# PANEL.net
KiCad netlist of a schematic drawn in Altium Designer
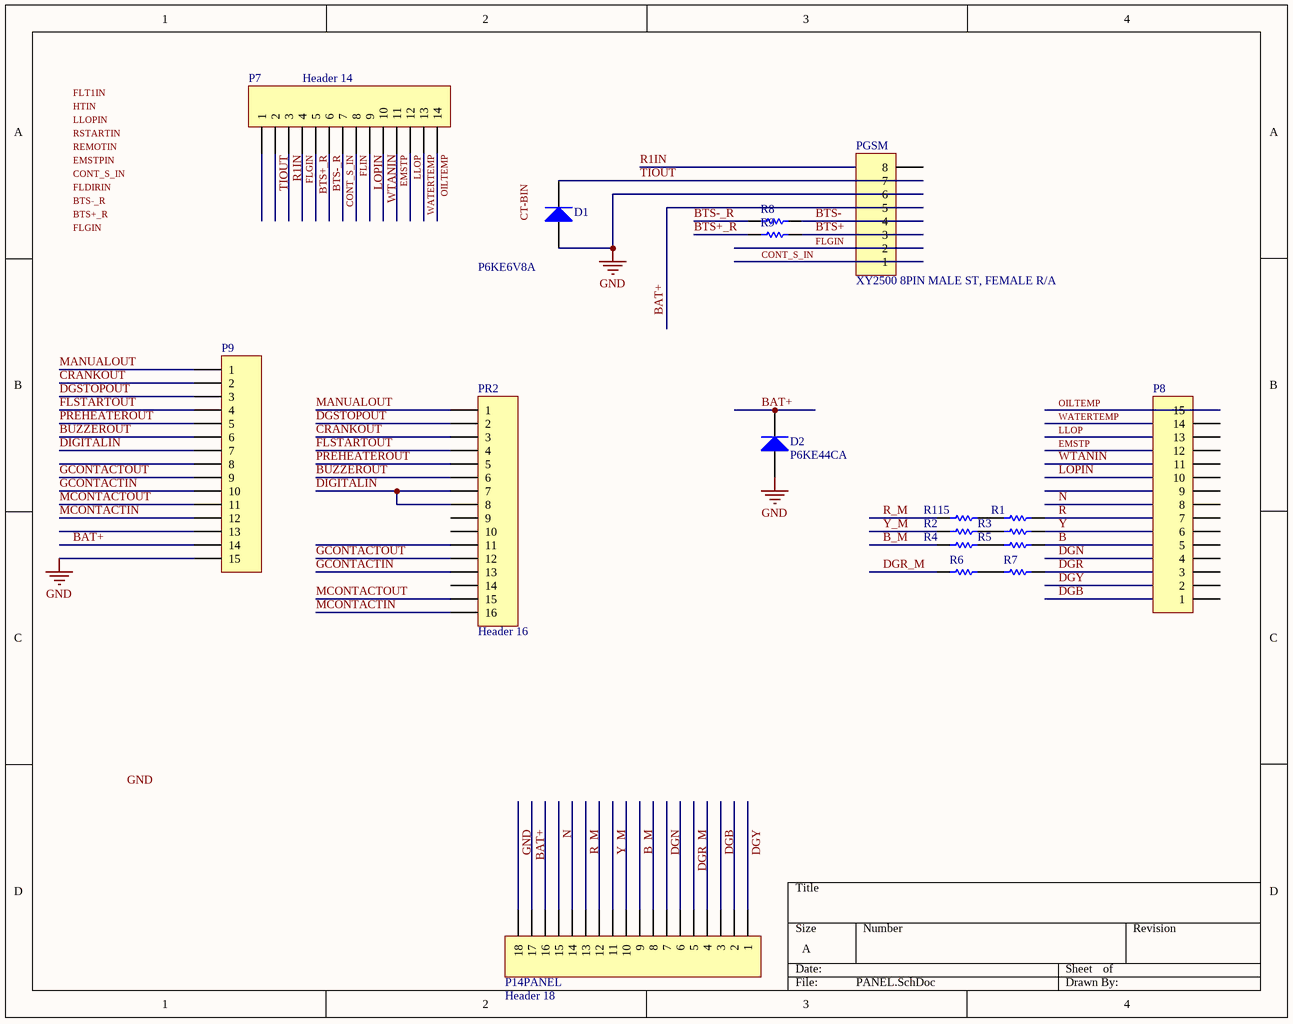
[diagram p0: PANEL.SchDoc]

(export (version "E")
  (design (tool "Eeschema 10.0.6"))
  (components
    (comp (ref "D1")
      (value "P6KE6V8A")
      (footprint "DIODE1A")
      (description "3 Amp Medium Power Silicon Rectifier Diode")
      (fields (field (name "PUBLISHER") "Altium Limited"))
      (libsource (lib "Miscellaneous Devices") (part "Diode 1N5408"))
    )
    (comp (ref "D2")
      (value "P6KE44CA")
      (footprint "DIODE1A")
      (description "3 Amp Medium Power Silicon Rectifier Diode")
      (fields (field (name "PUBLISHER") "Altium Limited"))
      (libsource (lib "Miscellaneous Devices") (part "Diode 1N5408"))
    )
    (comp (ref "P7")
      (value "Header 14")
      (footprint "HDR1X14_BURGE_M")
      (description "Header, 14-Pin")
      (fields (field (name "PUBLISHER") "Altium Limited"))
      (libsource (lib "Miscellaneous Connectors") (part "Header 14"))
    )
    (comp (ref "P8")
      (value "XY2500 7PIN+8PIN MALE ST, FEMALE R/A")
      (footprint "XY2500_15PIN_M_ST")
      (description "Header, 15-Pin")
      (fields (field (name "PUBLISHER") "Altium Limited"))
      (libsource (lib "") (part "Header 15_1"))
    )
    (comp (ref "P9")
      (value "XY2500 7PIN+8PIN MALE ST, FEMALE R/A")
      (footprint "XY2500_15PIN_M_ST")
      (description "Header, 15-Pin")
      (fields (field (name "PUBLISHER") "Altium Limited"))
      (libsource (lib "Miscellaneous Connectors") (part "Header 15"))
    )
    (comp (ref "P14PANEL")
      (value "Header 18")
      (footprint "HDR1X18_BURGE_M")
      (description "Header, 18-Pin")
      (fields (field (name "PUBLISHER") "Altium Limited"))
      (libsource (lib "Miscellaneous Connectors") (part "Header 18"))
    )
    (comp (ref "PGSM")
      (value "XY2500 8PIN MALE ST, FEMALE R/A")
      (footprint "XY2500_8PIN_M_ST")
      (description "Header, 8-Pin")
      (fields (field (name "PUBLISHER") "Altium Limited"))
      (libsource (lib "Miscellaneous Connectors") (part "Header 8"))
    )
    (comp (ref "PR2")
      (value "Header 16")
      (footprint "HDR1X16_BURGE_F")
      (description "Header, 16-Pin")
      (fields (field (name "PUBLISHER") "Altium Limited"))
      (libsource (lib "Miscellaneous Connectors") (part "Header 16"))
    )
    (comp (ref "R1")
      (value "MFR 1M .5W")
      (footprint "AXIAL-0.5")
      (description "Semiconductor Resistor")
      (fields (field (name "PUBLISHER") "Altium Limited"))
      (libsource (lib "Miscellaneous Devices") (part "Res Semi"))
    )
    (comp (ref "R2")
      (value "MFR 1M .5W")
      (footprint "AXIAL-0.5")
      (description "Semiconductor Resistor")
      (fields (field (name "PUBLISHER") "Altium Limited"))
      (libsource (lib "Miscellaneous Devices") (part "Res Semi"))
    )
    (comp (ref "R3")
      (value "MFR 1M .5W")
      (footprint "AXIAL-0.5")
      (description "Semiconductor Resistor")
      (fields (field (name "PUBLISHER") "Altium Limited"))
      (libsource (lib "Miscellaneous Devices") (part "Res Semi"))
    )
    (comp (ref "R4")
      (value "MFR 1M .5W")
      (footprint "AXIAL-0.5")
      (description "Semiconductor Resistor")
      (fields (field (name "PUBLISHER") "Altium Limited"))
      (libsource (lib "Miscellaneous Devices") (part "Res Semi"))
    )
    (comp (ref "R5")
      (value "MFR 1M .5W")
      (footprint "AXIAL-0.5")
      (description "Semiconductor Resistor")
      (fields (field (name "PUBLISHER") "Altium Limited"))
      (libsource (lib "Miscellaneous Devices") (part "Res Semi"))
    )
    (comp (ref "R6")
      (value "MFR 1M .5W")
      (footprint "AXIAL-0.5")
      (description "Semiconductor Resistor")
      (fields (field (name "PUBLISHER") "Altium Limited"))
      (libsource (lib "Miscellaneous Devices") (part "Res Semi"))
    )
    (comp (ref "R7")
      (value "MFR 1M .5W")
      (footprint "AXIAL-0.5")
      (description "Semiconductor Resistor")
      (fields (field (name "PUBLISHER") "Altium Limited"))
      (libsource (lib "Miscellaneous Devices") (part "Res Semi"))
    )
    (comp (ref "R8")
      (value "MFR 1M .5W")
      (footprint "AXIAL-0.5")
      (description "Semiconductor Resistor")
      (fields (field (name "PUBLISHER") "Altium Limited"))
      (libsource (lib "Miscellaneous Devices") (part "Res Semi"))
    )
    (comp (ref "R9")
      (value "MFR 1M .5W")
      (footprint "AXIAL-0.5")
      (description "Semiconductor Resistor")
      (fields (field (name "PUBLISHER") "Altium Limited"))
      (libsource (lib "Miscellaneous Devices") (part "Res Semi"))
    )
    (comp (ref "R115")
      (value "MFR 1M .5W")
      (footprint "AXIAL-0.5")
      (description "Semiconductor Resistor")
      (fields (field (name "PUBLISHER") "Altium Limited"))
      (libsource (lib "Miscellaneous Devices") (part "Res Semi"))
    )
  )
  (nets
    (net (code "1") (name "/B") (class "Default")
      (node (ref "P8") (pin "5") (pinfunction "5_5") (pintype "passive"))
      (node (ref "R5") (pin "2") (pinfunction "2_2") (pintype "passive"))
    )
    (net (code "2") (name "/BAT+") (class "Default")
      (node (ref "D2") (pin "2") (pinfunction "K_2") (pintype "passive"))
      (node (ref "P14PANEL") (pin "17") (pinfunction "17_17") (pintype "passive"))
      (node (ref "P9") (pin "14") (pinfunction "14_14") (pintype "passive"))
      (node (ref "PGSM") (pin "5") (pinfunction "5_5") (pintype "passive"))
    )
    (net (code "3") (name "/BTS+") (class "Default")
      (node (ref "PGSM") (pin "3") (pinfunction "3_3") (pintype "passive"))
      (node (ref "R9") (pin "2") (pinfunction "2_2") (pintype "passive"))
    )
    (net (code "4") (name "/BTS+_R") (class "Default")
      (node (ref "P7") (pin "5") (pinfunction "5_5") (pintype "passive"))
      (node (ref "R9") (pin "1") (pinfunction "1_1") (pintype "passive"))
    )
    (net (code "5") (name "/BTS-") (class "Default")
      (node (ref "PGSM") (pin "4") (pinfunction "4_4") (pintype "passive"))
      (node (ref "R8") (pin "2") (pinfunction "2_2") (pintype "passive"))
    )
    (net (code "6") (name "/BTS-_R") (class "Default")
      (node (ref "P7") (pin "6") (pinfunction "6_6") (pintype "passive"))
      (node (ref "R8") (pin "1") (pinfunction "1_1") (pintype "passive"))
    )
    (net (code "7") (name "/BUZZEROUT") (class "Default")
      (node (ref "P9") (pin "6") (pinfunction "6_6") (pintype "passive"))
      (node (ref "PR2") (pin "6") (pinfunction "6_6") (pintype "passive"))
    )
    (net (code "8") (name "/B_M") (class "Default")
      (node (ref "P14PANEL") (pin "9") (pinfunction "9_9") (pintype "passive"))
      (node (ref "R4") (pin "1") (pinfunction "1_1") (pintype "passive"))
    )
    (net (code "9") (name "/CONT_S_IN") (class "Default")
      (node (ref "P7") (pin "7") (pinfunction "7_7") (pintype "passive"))
      (node (ref "PGSM") (pin "1") (pinfunction "1_1") (pintype "passive"))
    )
    (net (code "10") (name "/CRANKOUT") (class "Default")
      (node (ref "P9") (pin "2") (pinfunction "2_2") (pintype "passive"))
      (node (ref "PR2") (pin "3") (pinfunction "3_3") (pintype "passive"))
    )
    (net (code "12") (name "/DGB") (class "Default")
      (node (ref "P14PANEL") (pin "3") (pinfunction "3_3") (pintype "passive"))
      (node (ref "P8") (pin "1") (pinfunction "1_1") (pintype "passive"))
    )
    (net (code "13") (name "/DGN") (class "Default")
      (node (ref "P14PANEL") (pin "7") (pinfunction "7_7") (pintype "passive"))
      (node (ref "P8") (pin "4") (pinfunction "4_4") (pintype "passive"))
    )
    (net (code "14") (name "/DGR") (class "Default")
      (node (ref "P8") (pin "3") (pinfunction "3_3") (pintype "passive"))
      (node (ref "R7") (pin "2") (pinfunction "2_2") (pintype "passive"))
    )
    (net (code "15") (name "/DGR_M") (class "Default")
      (node (ref "P14PANEL") (pin "5") (pinfunction "5_5") (pintype "passive"))
      (node (ref "R6") (pin "1") (pinfunction "1_1") (pintype "passive"))
    )
    (net (code "16") (name "/DGSTOPOUT") (class "Default")
      (node (ref "P9") (pin "3") (pinfunction "3_3") (pintype "passive"))
      (node (ref "PR2") (pin "2") (pinfunction "2_2") (pintype "passive"))
    )
    (net (code "17") (name "/DGY") (class "Default")
      (node (ref "P14PANEL") (pin "1") (pinfunction "1_1") (pintype "passive"))
      (node (ref "P8") (pin "2") (pinfunction "2_2") (pintype "passive"))
    )
    (net (code "18") (name "/DIGITALIN") (class "Default")
      (node (ref "P9") (pin "7") (pinfunction "7_7") (pintype "passive"))
      (node (ref "PR2") (pin "7") (pinfunction "7_7") (pintype "passive"))
      (node (ref "PR2") (pin "8") (pinfunction "8_8") (pintype "passive"))
    )
    (net (code "19") (name "/EMSTP") (class "Default")
      (node (ref "P7") (pin "11") (pinfunction "11_11") (pintype "passive"))
      (node (ref "P8") (pin "12") (pinfunction "12_12") (pintype "passive"))
    )
    (net (code "22") (name "/FLGIN") (class "Default")
      (node (ref "P7") (pin "4") (pinfunction "4_4") (pintype "passive"))
      (node (ref "PGSM") (pin "2") (pinfunction "2_2") (pintype "passive"))
    )
    (net (code "23") (name "/FLIN") (class "Default")
      (node (ref "P7") (pin "8") (pinfunction "8_8") (pintype "passive"))
    )
    (net (code "24") (name "/FLSTARTOUT") (class "Default")
      (node (ref "P9") (pin "4") (pinfunction "4_4") (pintype "passive"))
      (node (ref "PR2") (pin "4") (pinfunction "4_4") (pintype "passive"))
    )
    (net (code "26") (name "/GCONTACTIN") (class "Default")
      (node (ref "P9") (pin "10") (pinfunction "10_10") (pintype "passive"))
      (node (ref "PR2") (pin "13") (pinfunction "13_13") (pintype "passive"))
    )
    (net (code "27") (name "/GCONTACTOUT") (class "Default")
      (node (ref "P9") (pin "9") (pinfunction "9_9") (pintype "passive"))
      (node (ref "PR2") (pin "12") (pinfunction "12_12") (pintype "passive"))
    )
    (net (code "29") (name "/LLOP") (class "Default")
      (node (ref "P7") (pin "12") (pinfunction "12_12") (pintype "passive"))
      (node (ref "P8") (pin "13") (pinfunction "13_13") (pintype "passive"))
    )
    (net (code "31") (name "/LOPIN") (class "Default")
      (node (ref "P7") (pin "9") (pinfunction "9_9") (pintype "passive"))
      (node (ref "P8") (pin "10") (pinfunction "10_10") (pintype "passive"))
    )
    (net (code "32") (name "/MANUALOUT") (class "Default")
      (node (ref "P9") (pin "1") (pinfunction "1_1") (pintype "passive"))
      (node (ref "PR2") (pin "1") (pinfunction "1_1") (pintype "passive"))
    )
    (net (code "33") (name "/MCONTACTIN") (class "Default")
      (node (ref "P9") (pin "12") (pinfunction "12_12") (pintype "passive"))
      (node (ref "PR2") (pin "16") (pinfunction "16_16") (pintype "passive"))
    )
    (net (code "34") (name "/MCONTACTOUT") (class "Default")
      (node (ref "P9") (pin "11") (pinfunction "11_11") (pintype "passive"))
      (node (ref "PR2") (pin "15") (pinfunction "15_15") (pintype "passive"))
    )
    (net (code "35") (name "/N") (class "Default")
      (node (ref "P14PANEL") (pin "15") (pinfunction "15_15") (pintype "passive"))
      (node (ref "P8") (pin "8") (pinfunction "8_8") (pintype "passive"))
    )
    (net (code "36") (name "/OILTEMP") (class "Default")
      (node (ref "P7") (pin "14") (pinfunction "14_14") (pintype "passive"))
      (node (ref "P8") (pin "15") (pinfunction "15_15") (pintype "passive"))
    )
    (net (code "37") (name "/PREHEATEROUT") (class "Default")
      (node (ref "P9") (pin "5") (pinfunction "5_5") (pintype "passive"))
      (node (ref "PR2") (pin "5") (pinfunction "5_5") (pintype "passive"))
    )
    (net (code "38") (name "/R") (class "Default")
      (node (ref "P8") (pin "7") (pinfunction "7_7") (pintype "passive"))
      (node (ref "R1") (pin "2") (pinfunction "2_2") (pintype "passive"))
    )
    (net (code "39") (name "/R1IN") (class "Default")
      (node (ref "P7") (pin "3") (pinfunction "3_3") (pintype "passive"))
      (node (ref "PGSM") (pin "8") (pinfunction "8_8") (pintype "passive"))
    )
    (net (code "42") (name "/R_M") (class "Default")
      (node (ref "P14PANEL") (pin "13") (pinfunction "13_13") (pintype "passive"))
      (node (ref "R115") (pin "1") (pinfunction "1_1") (pintype "passive"))
    )
    (net (code "43") (name "/TIOUT") (class "Default")
      (node (ref "D1") (pin "2") (pinfunction "K_2") (pintype "passive"))
      (node (ref "P7") (pin "2") (pinfunction "2_2") (pintype "passive"))
      (node (ref "PGSM") (pin "7") (pinfunction "7_7") (pintype "passive"))
    )
    (net (code "44") (name "/WATERTEMP") (class "Default")
      (node (ref "P7") (pin "13") (pinfunction "13_13") (pintype "passive"))
      (node (ref "P8") (pin "14") (pinfunction "14_14") (pintype "passive"))
    )
    (net (code "45") (name "/WTANIN") (class "Default")
      (node (ref "P7") (pin "10") (pinfunction "10_10") (pintype "passive"))
      (node (ref "P8") (pin "11") (pinfunction "11_11") (pintype "passive"))
    )
    (net (code "46") (name "/Y") (class "Default")
      (node (ref "P8") (pin "6") (pinfunction "6_6") (pintype "passive"))
      (node (ref "R3") (pin "2") (pinfunction "2_2") (pintype "passive"))
    )
    (net (code "47") (name "/Y_M") (class "Default")
      (node (ref "P14PANEL") (pin "11") (pinfunction "11_11") (pintype "passive"))
      (node (ref "R2") (pin "1") (pinfunction "1_1") (pintype "passive"))
    )
    (net (code "48") (name "GND") (class "Default")
      (node (ref "D1") (pin "1") (pinfunction "A_1") (pintype "passive"))
      (node (ref "D2") (pin "1") (pinfunction "A_1") (pintype "passive"))
      (node (ref "P14PANEL") (pin "18") (pinfunction "18_18") (pintype "passive"))
      (node (ref "P9") (pin "15") (pinfunction "15_15") (pintype "passive"))
      (node (ref "PGSM") (pin "6") (pinfunction "6_6") (pintype "passive"))
    )
    (net (code "49") (name "Net-(R1-Pad1)") (class "Default")
      (node (ref "R1") (pin "1") (pinfunction "1_1") (pintype "passive"))
      (node (ref "R115") (pin "2") (pinfunction "2_2") (pintype "passive"))
    )
    (net (code "50") (name "Net-(R2-Pad2)") (class "Default")
      (node (ref "R2") (pin "2") (pinfunction "2_2") (pintype "passive"))
      (node (ref "R3") (pin "1") (pinfunction "1_1") (pintype "passive"))
    )
    (net (code "51") (name "Net-(R4-Pad2)") (class "Default")
      (node (ref "R4") (pin "2") (pinfunction "2_2") (pintype "passive"))
      (node (ref "R5") (pin "1") (pinfunction "1_1") (pintype "passive"))
    )
    (net (code "52") (name "Net-(R6-Pad2)") (class "Default")
      (node (ref "R6") (pin "2") (pinfunction "2_2") (pintype "passive"))
      (node (ref "R7") (pin "1") (pinfunction "1_1") (pintype "passive"))
    )
    (net (code "53") (name "unconnected-(P7-Pad1)") (class "Default")
      (node (ref "P7") (pin "1") (pinfunction "1_1") (pintype "passive"))
    )
    (net (code "54") (name "unconnected-(P8-Pad9)") (class "Default")
      (node (ref "P8") (pin "9") (pinfunction "9_9") (pintype "passive"))
    )
    (net (code "55") (name "unconnected-(P9-Pad8)") (class "Default")
      (node (ref "P9") (pin "8") (pinfunction "8_8") (pintype "passive"))
    )
    (net (code "56") (name "unconnected-(P9-Pad13)") (class "Default")
      (node (ref "P9") (pin "13") (pinfunction "13_13") (pintype "passive"))
    )
    (net (code "57") (name "unconnected-(P14PANEL-Pad2)") (class "Default")
      (node (ref "P14PANEL") (pin "2") (pinfunction "2_2") (pintype "passive"))
    )
    (net (code "58") (name "unconnected-(P14PANEL-Pad4)") (class "Default")
      (node (ref "P14PANEL") (pin "4") (pinfunction "4_4") (pintype "passive"))
    )
    (net (code "59") (name "unconnected-(P14PANEL-Pad6)") (class "Default")
      (node (ref "P14PANEL") (pin "6") (pinfunction "6_6") (pintype "passive"))
    )
    (net (code "60") (name "unconnected-(P14PANEL-Pad8)") (class "Default")
      (node (ref "P14PANEL") (pin "8") (pinfunction "8_8") (pintype "passive"))
    )
    (net (code "61") (name "unconnected-(P14PANEL-Pad10)") (class "Default")
      (node (ref "P14PANEL") (pin "10") (pinfunction "10_10") (pintype "passive"))
    )
    (net (code "62") (name "unconnected-(P14PANEL-Pad12)") (class "Default")
      (node (ref "P14PANEL") (pin "12") (pinfunction "12_12") (pintype "passive"))
    )
    (net (code "63") (name "unconnected-(P14PANEL-Pad14)") (class "Default")
      (node (ref "P14PANEL") (pin "14") (pinfunction "14_14") (pintype "passive"))
    )
    (net (code "64") (name "unconnected-(P14PANEL-Pad16)") (class "Default")
      (node (ref "P14PANEL") (pin "16") (pinfunction "16_16") (pintype "passive"))
    )
    (net (code "65") (name "unconnected-(PR2-Pad9)") (class "Default")
      (node (ref "PR2") (pin "9") (pinfunction "9_9") (pintype "passive"))
    )
    (net (code "66") (name "unconnected-(PR2-Pad10)") (class "Default")
      (node (ref "PR2") (pin "10") (pinfunction "10_10") (pintype "passive"))
    )
    (net (code "67") (name "unconnected-(PR2-Pad11)") (class "Default")
      (node (ref "PR2") (pin "11") (pinfunction "11_11") (pintype "passive"))
    )
    (net (code "68") (name "unconnected-(PR2-Pad14)") (class "Default")
      (node (ref "PR2") (pin "14") (pinfunction "14_14") (pintype "passive"))
    )
  )
)
